# placaOscilador_TP1_ASSD.net
KiCad netlist of a schematic drawn in Altium Designer
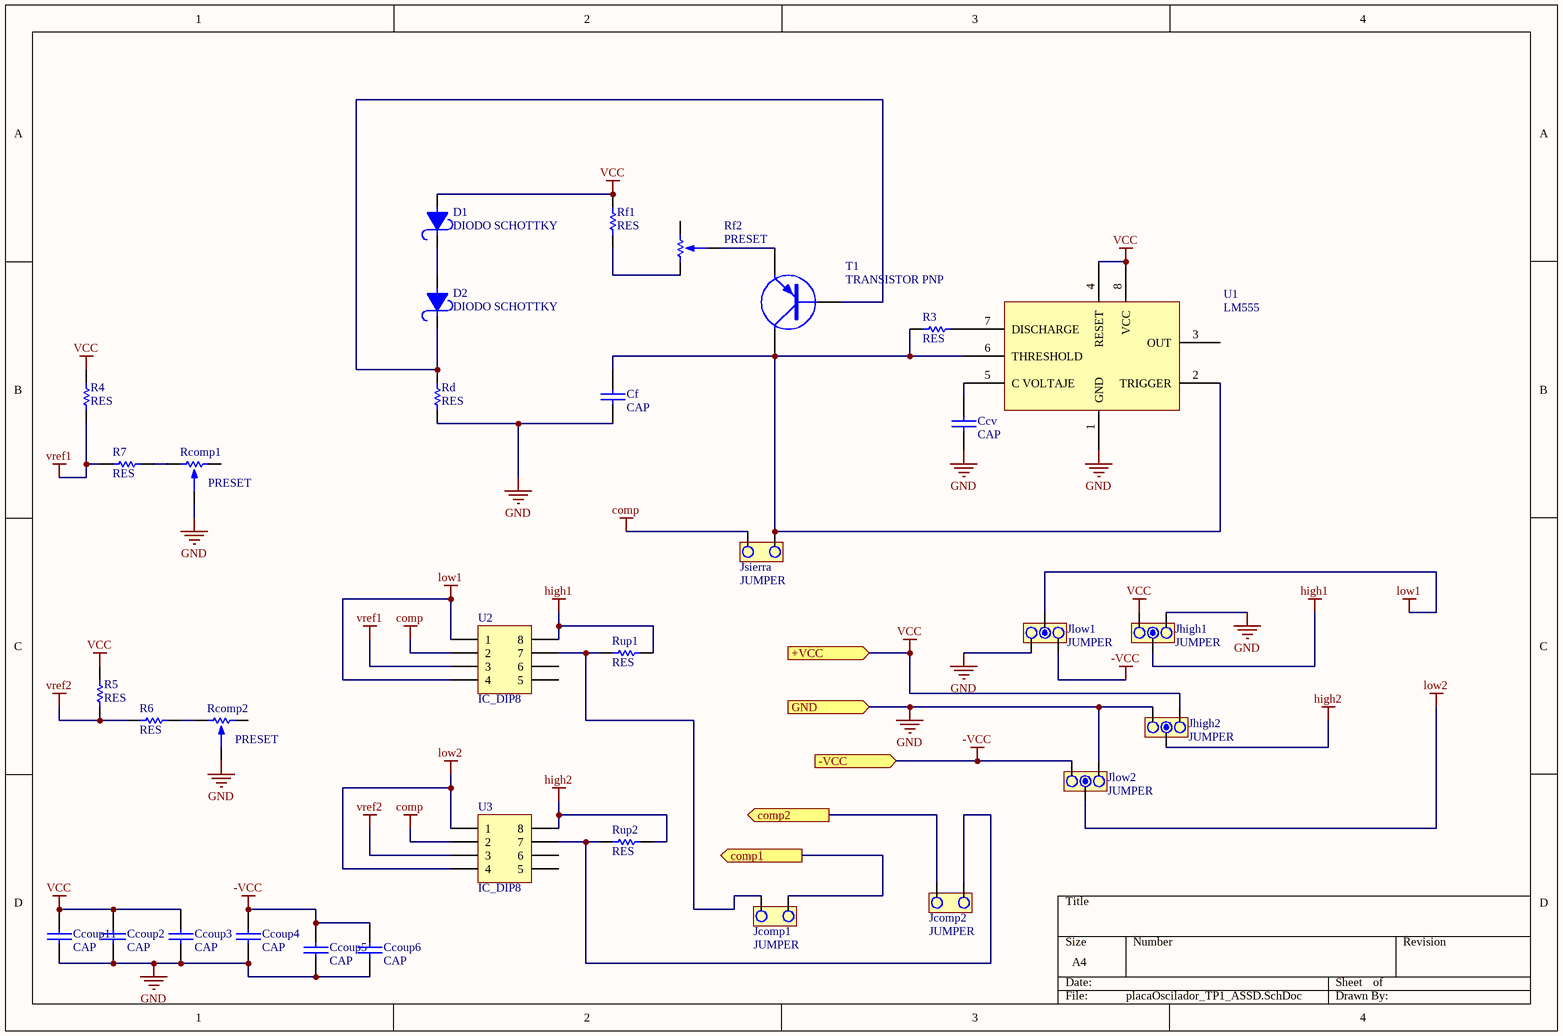
[diagram p0: placaOscilador_TP1_ASSD.SchDoc]

(export (version "E")
  (design (tool "Eeschema 10.0.6"))
  (components
    (comp (ref "Ccoup2") (value "CAP") (footprint "CAP200") (libsource (lib "LIBEBAL") (part "CAP")))
    (comp (ref "Ccoup3") (value "CAP") (footprint "CAP200") (libsource (lib "LIBEBAL") (part "CAP")))
    (comp (ref "Ccoup4") (value "CAP") (footprint "CAP200") (libsource (lib "LIBEBAL") (part "CAP")))
    (comp (ref "Ccoup5") (value "CAP") (footprint "CAP200") (libsource (lib "LIBEBAL") (part "CAP")))
    (comp (ref "Ccoup6") (value "CAP") (footprint "CAP200") (libsource (lib "LIBEBAL") (part "CAP")))
    (comp (ref "Ccoup11") (value "CAP") (footprint "CAP200") (libsource (lib "LIBEBAL") (part "CAP")))
    (comp (ref "Ccv") (value "CAP") (footprint "CAP200") (libsource (lib "LIBEBAL") (part "CAP")))
    (comp (ref "Cf") (value "CAP") (footprint "CAP200") (libsource (lib "LIBEBAL") (part "CAP")))
    (comp (ref "D1")
      (value "DIODO SCHOTTKY")
      (footprint "DO41")
      (libsource (lib "LIBEBAL") (part "DIODO SCHOTTKY"))
    )
    (comp (ref "D2")
      (value "DIODO SCHOTTKY")
      (footprint "DO41")
      (libsource (lib "LIBEBAL") (part "DIODO SCHOTTKY"))
    )
    (comp (ref "Jcomp1") (value "JUMPER") (footprint "JUMPER2") (libsource (lib "LIBEBAL") (part "JUMPER")))
    (comp (ref "Jcomp2") (value "JUMPER") (footprint "JUMPER2") (libsource (lib "LIBEBAL") (part "JUMPER")))
    (comp (ref "Jhigh1") (value "JUMPER") (footprint "JUMPER3") (libsource (lib "LIBEBAL") (part "JUMPER3")))
    (comp (ref "Jhigh2") (value "JUMPER") (footprint "JUMPER3") (libsource (lib "LIBEBAL") (part "JUMPER3")))
    (comp (ref "Jlow1") (value "JUMPER") (footprint "JUMPER3") (libsource (lib "") (part "JUMPER3_1")))
    (comp (ref "Jlow2") (value "JUMPER") (footprint "JUMPER3") (libsource (lib "LIBEBAL") (part "JUMPER3")))
    (comp (ref "Jsierra") (value "JUMPER") (footprint "JUMPER2") (libsource (lib "LIBEBAL") (part "JUMPER")))
    (comp (ref "R3") (value "RES") (footprint "RES300") (libsource (lib "LIBEBAL") (part "RES")))
    (comp (ref "R4") (value "RES") (footprint "RES300") (libsource (lib "LIBEBAL") (part "RES")))
    (comp (ref "R5") (value "RES") (footprint "RES300") (libsource (lib "LIBEBAL") (part "RES")))
    (comp (ref "R6") (value "RES") (footprint "RES300") (libsource (lib "LIBEBAL") (part "RES")))
    (comp (ref "R7") (value "RES") (footprint "RES300") (libsource (lib "LIBEBAL") (part "RES")))
    (comp (ref "Rcomp1") (value "PRESET") (footprint "PRESET V") (libsource (lib "LIBEBAL") (part "PRESET")))
    (comp (ref "Rcomp2") (value "PRESET") (footprint "PRESET V") (libsource (lib "LIBEBAL") (part "PRESET")))
    (comp (ref "Rd") (value "RES") (footprint "RES300") (libsource (lib "LIBEBAL") (part "RES")))
    (comp (ref "Rf1") (value "RES") (footprint "RES300") (libsource (lib "LIBEBAL") (part "RES")))
    (comp (ref "Rf2") (value "PRESET") (footprint "PRESET V") (libsource (lib "LIBEBAL") (part "PRESET")))
    (comp (ref "Rup1") (value "RES") (footprint "RES300") (libsource (lib "LIBEBAL") (part "RES")))
    (comp (ref "Rup2") (value "RES") (footprint "RES300") (libsource (lib "LIBEBAL") (part "RES")))
    (comp (ref "T1")
      (value "TRANSISTOR PNP")
      (footprint "TO92")
      (libsource (lib "LIBEBAL") (part "TRANSISTOR PNP"))
    )
    (comp (ref "U1")
      (value "LM555")
      (footprint "DIP8")
      (description "Timer")
      (libsource (lib "LIBEBAL") (part "LM555"))
    )
    (comp (ref "U2") (value "IC_DIP8") (footprint "DIP8") (libsource (lib "LIBEBAL") (part "IC_DIP8")))
    (comp (ref "U3") (value "IC_DIP8") (footprint "DIP8") (libsource (lib "LIBEBAL") (part "IC_DIP8")))
  )
  (nets
    (net (code "1") (name "-VCC") (class "Default")
      (node (ref "Ccoup4") (pin "1") (pinfunction "1_1") (pintype "passive"))
      (node (ref "Ccoup5") (pin "1") (pinfunction "1_1") (pintype "passive"))
      (node (ref "Ccoup6") (pin "1") (pinfunction "1_1") (pintype "passive"))
      (node (ref "Jlow1") (pin "1") (pinfunction "1_1") (pintype "passive"))
      (node (ref "Jlow2") (pin "1") (pinfunction "1_1") (pintype "passive"))
    )
    (net (code "2") (name "/comp1") (class "Default")
      (node (ref "Jcomp1") (pin "2") (pinfunction "2_2") (pintype "passive"))
    )
    (net (code "3") (name "/comp2") (class "Default")
      (node (ref "Jcomp2") (pin "1") (pinfunction "1_1") (pintype "passive"))
    )
    (net (code "4") (name "GND") (class "Default")
      (node (ref "Ccoup11") (pin "2") (pinfunction "2_2") (pintype "passive"))
      (node (ref "Ccoup2") (pin "2") (pinfunction "2_2") (pintype "passive"))
      (node (ref "Ccoup3") (pin "2") (pinfunction "2_2") (pintype "passive"))
      (node (ref "Ccoup4") (pin "2") (pinfunction "2_2") (pintype "passive"))
      (node (ref "Ccoup5") (pin "2") (pinfunction "2_2") (pintype "passive"))
      (node (ref "Ccoup6") (pin "2") (pinfunction "2_2") (pintype "passive"))
      (node (ref "Ccv") (pin "2") (pinfunction "2_2") (pintype "passive"))
      (node (ref "Cf") (pin "2") (pinfunction "2_2") (pintype "passive"))
      (node (ref "Jhigh1") (pin "3") (pinfunction "3_3") (pintype "passive"))
      (node (ref "Jhigh2") (pin "1") (pinfunction "1_1") (pintype "passive"))
      (node (ref "Jlow1") (pin "3") (pinfunction "3_3") (pintype "passive"))
      (node (ref "Jlow2") (pin "3") (pinfunction "3_3") (pintype "passive"))
      (node (ref "Rcomp1") (pin "2") (pinfunction "2_2") (pintype "passive"))
      (node (ref "Rcomp2") (pin "2") (pinfunction "2_2") (pintype "passive"))
      (node (ref "Rd") (pin "1") (pinfunction "1_1") (pintype "passive"))
      (node (ref "U1") (pin "1") (pinfunction "GND_1") (pintype "passive"))
    )
    (net (code "5") (name "Net-(D1-Pad2)") (class "Default")
      (node (ref "D1") (pin "2") (pinfunction "2_2") (pintype "passive"))
      (node (ref "D2") (pin "1") (pinfunction "1_1") (pintype "passive"))
    )
    (net (code "6") (name "Net-(Jcomp1-Pad1)") (class "Default")
      (node (ref "Jcomp1") (pin "1") (pinfunction "1_1") (pintype "passive"))
      (node (ref "Rup1") (pin "1") (pinfunction "1_1") (pintype "passive"))
      (node (ref "U2") (pin "7") (pinfunction "7_7") (pintype "passive"))
    )
    (net (code "7") (name "Net-(Jcomp2-Pad2)") (class "Default")
      (node (ref "Jcomp2") (pin "2") (pinfunction "2_2") (pintype "passive"))
      (node (ref "Rup2") (pin "1") (pinfunction "1_1") (pintype "passive"))
      (node (ref "U3") (pin "7") (pinfunction "7_7") (pintype "passive"))
    )
    (net (code "8") (name "Net-(R6-Pad2)") (class "Default")
      (node (ref "R6") (pin "2") (pinfunction "2_2") (pintype "passive"))
      (node (ref "Rcomp2") (pin "3") (pinfunction "3_3") (pintype "passive"))
    )
    (net (code "9") (name "Net-(R7-Pad2)") (class "Default")
      (node (ref "R7") (pin "2") (pinfunction "2_2") (pintype "passive"))
      (node (ref "Rcomp1") (pin "3") (pinfunction "3_3") (pintype "passive"))
    )
    (net (code "10") (name "Net-(Rf1-Pad1)") (class "Default")
      (node (ref "Rf1") (pin "1") (pinfunction "1_1") (pintype "passive"))
      (node (ref "Rf2") (pin "3") (pinfunction "3_3") (pintype "passive"))
    )
    (net (code "11") (name "Net-(T1-B)") (class "Default")
      (node (ref "D2") (pin "2") (pinfunction "2_2") (pintype "passive"))
      (node (ref "Rd") (pin "2") (pinfunction "2_2") (pintype "passive"))
      (node (ref "T1") (pin "1") (pinfunction "B_1") (pintype "passive"))
    )
    (net (code "12") (name "Net-(T1-C)") (class "Default")
      (node (ref "Cf") (pin "1") (pinfunction "1_1") (pintype "passive"))
      (node (ref "Jsierra") (pin "2") (pinfunction "2_2") (pintype "passive"))
      (node (ref "R3") (pin "1") (pinfunction "1_1") (pintype "passive"))
      (node (ref "T1") (pin "2") (pinfunction "C_2") (pintype "passive"))
      (node (ref "U1") (pin "2") (pinfunction "TRIGGER_2") (pintype "passive"))
      (node (ref "U1") (pin "6") (pinfunction "THRESHOLD_6") (pintype "passive"))
    )
    (net (code "13") (name "Net-(T1-E)") (class "Default")
      (node (ref "Rf2") (pin "2") (pinfunction "2_2") (pintype "passive"))
      (node (ref "T1") (pin "3") (pinfunction "E_3") (pintype "passive"))
    )
    (net (code "14") (name "Net-(U1-C_VOLTAJE)") (class "Default")
      (node (ref "Ccv") (pin "1") (pinfunction "1_1") (pintype "passive"))
      (node (ref "U1") (pin "5") (pinfunction "C_VOLTAJE_5") (pintype "passive"))
    )
    (net (code "15") (name "Net-(U1-DISCHARGE)") (class "Default")
      (node (ref "R3") (pin "2") (pinfunction "2_2") (pintype "passive"))
      (node (ref "U1") (pin "7") (pinfunction "DISCHARGE_7") (pintype "passive"))
    )
    (net (code "16") (name "VCC") (class "Default")
      (node (ref "Ccoup11") (pin "1") (pinfunction "1_1") (pintype "passive"))
      (node (ref "Ccoup2") (pin "1") (pinfunction "1_1") (pintype "passive"))
      (node (ref "Ccoup3") (pin "1") (pinfunction "1_1") (pintype "passive"))
      (node (ref "D1") (pin "1") (pinfunction "1_1") (pintype "passive"))
      (node (ref "Jhigh1") (pin "1") (pinfunction "1_1") (pintype "passive"))
      (node (ref "Jhigh2") (pin "3") (pinfunction "3_3") (pintype "passive"))
      (node (ref "R4") (pin "2") (pinfunction "2_2") (pintype "passive"))
      (node (ref "R5") (pin "2") (pinfunction "2_2") (pintype "passive"))
      (node (ref "Rf1") (pin "2") (pinfunction "2_2") (pintype "passive"))
      (node (ref "U1") (pin "4") (pinfunction "RESET_4") (pintype "passive"))
      (node (ref "U1") (pin "8") (pinfunction "VCC_8") (pintype "passive"))
    )
    (net (code "17") (name "comp") (class "Default")
      (node (ref "Jsierra") (pin "1") (pinfunction "1_1") (pintype "passive"))
      (node (ref "U2") (pin "2") (pinfunction "2_2") (pintype "passive"))
      (node (ref "U3") (pin "2") (pinfunction "2_2") (pintype "passive"))
    )
    (net (code "18") (name "high1") (class "Default")
      (node (ref "Jhigh1") (pin "2") (pinfunction "2_2") (pintype "passive"))
      (node (ref "Rup1") (pin "2") (pinfunction "2_2") (pintype "passive"))
      (node (ref "U2") (pin "8") (pinfunction "8_8") (pintype "passive"))
    )
    (net (code "19") (name "high2") (class "Default")
      (node (ref "Jhigh2") (pin "2") (pinfunction "2_2") (pintype "passive"))
      (node (ref "Rup2") (pin "2") (pinfunction "2_2") (pintype "passive"))
      (node (ref "U3") (pin "8") (pinfunction "8_8") (pintype "passive"))
    )
    (net (code "20") (name "low1") (class "Default")
      (node (ref "Jlow1") (pin "2") (pinfunction "2_2") (pintype "passive"))
      (node (ref "U2") (pin "1") (pinfunction "1_1") (pintype "passive"))
      (node (ref "U2") (pin "4") (pinfunction "4_4") (pintype "passive"))
    )
    (net (code "21") (name "low2") (class "Default")
      (node (ref "Jlow2") (pin "2") (pinfunction "2_2") (pintype "passive"))
      (node (ref "U3") (pin "1") (pinfunction "1_1") (pintype "passive"))
      (node (ref "U3") (pin "4") (pinfunction "4_4") (pintype "passive"))
    )
    (net (code "22") (name "unconnected-(Rcomp1-Pad1)") (class "Default")
      (node (ref "Rcomp1") (pin "1") (pinfunction "1_1") (pintype "passive"))
    )
    (net (code "23") (name "unconnected-(Rcomp2-Pad1)") (class "Default")
      (node (ref "Rcomp2") (pin "1") (pinfunction "1_1") (pintype "passive"))
    )
    (net (code "24") (name "unconnected-(Rf2-Pad1)") (class "Default")
      (node (ref "Rf2") (pin "1") (pinfunction "1_1") (pintype "passive"))
    )
    (net (code "25") (name "unconnected-(U1-OUT-Pad3)") (class "Default")
      (node (ref "U1") (pin "3") (pinfunction "OUT_3") (pintype "passive"))
    )
    (net (code "26") (name "unconnected-(U2-Pad5)") (class "Default")
      (node (ref "U2") (pin "5") (pinfunction "5_5") (pintype "passive"))
    )
    (net (code "27") (name "unconnected-(U2-Pad6)") (class "Default")
      (node (ref "U2") (pin "6") (pinfunction "6_6") (pintype "passive"))
    )
    (net (code "28") (name "unconnected-(U3-Pad5)") (class "Default")
      (node (ref "U3") (pin "5") (pinfunction "5_5") (pintype "passive"))
    )
    (net (code "29") (name "unconnected-(U3-Pad6)") (class "Default")
      (node (ref "U3") (pin "6") (pinfunction "6_6") (pintype "passive"))
    )
    (net (code "30") (name "vref1") (class "Default")
      (node (ref "R4") (pin "1") (pinfunction "1_1") (pintype "passive"))
      (node (ref "R7") (pin "1") (pinfunction "1_1") (pintype "passive"))
      (node (ref "U2") (pin "3") (pinfunction "3_3") (pintype "passive"))
    )
    (net (code "31") (name "vref2") (class "Default")
      (node (ref "R5") (pin "1") (pinfunction "1_1") (pintype "passive"))
      (node (ref "R6") (pin "1") (pinfunction "1_1") (pintype "passive"))
      (node (ref "U3") (pin "3") (pinfunction "3_3") (pintype "passive"))
    )
  )
)
